# Matrix_Buttons_v0_0_1.net
KiCad netlist of a schematic drawn in Altium Designer
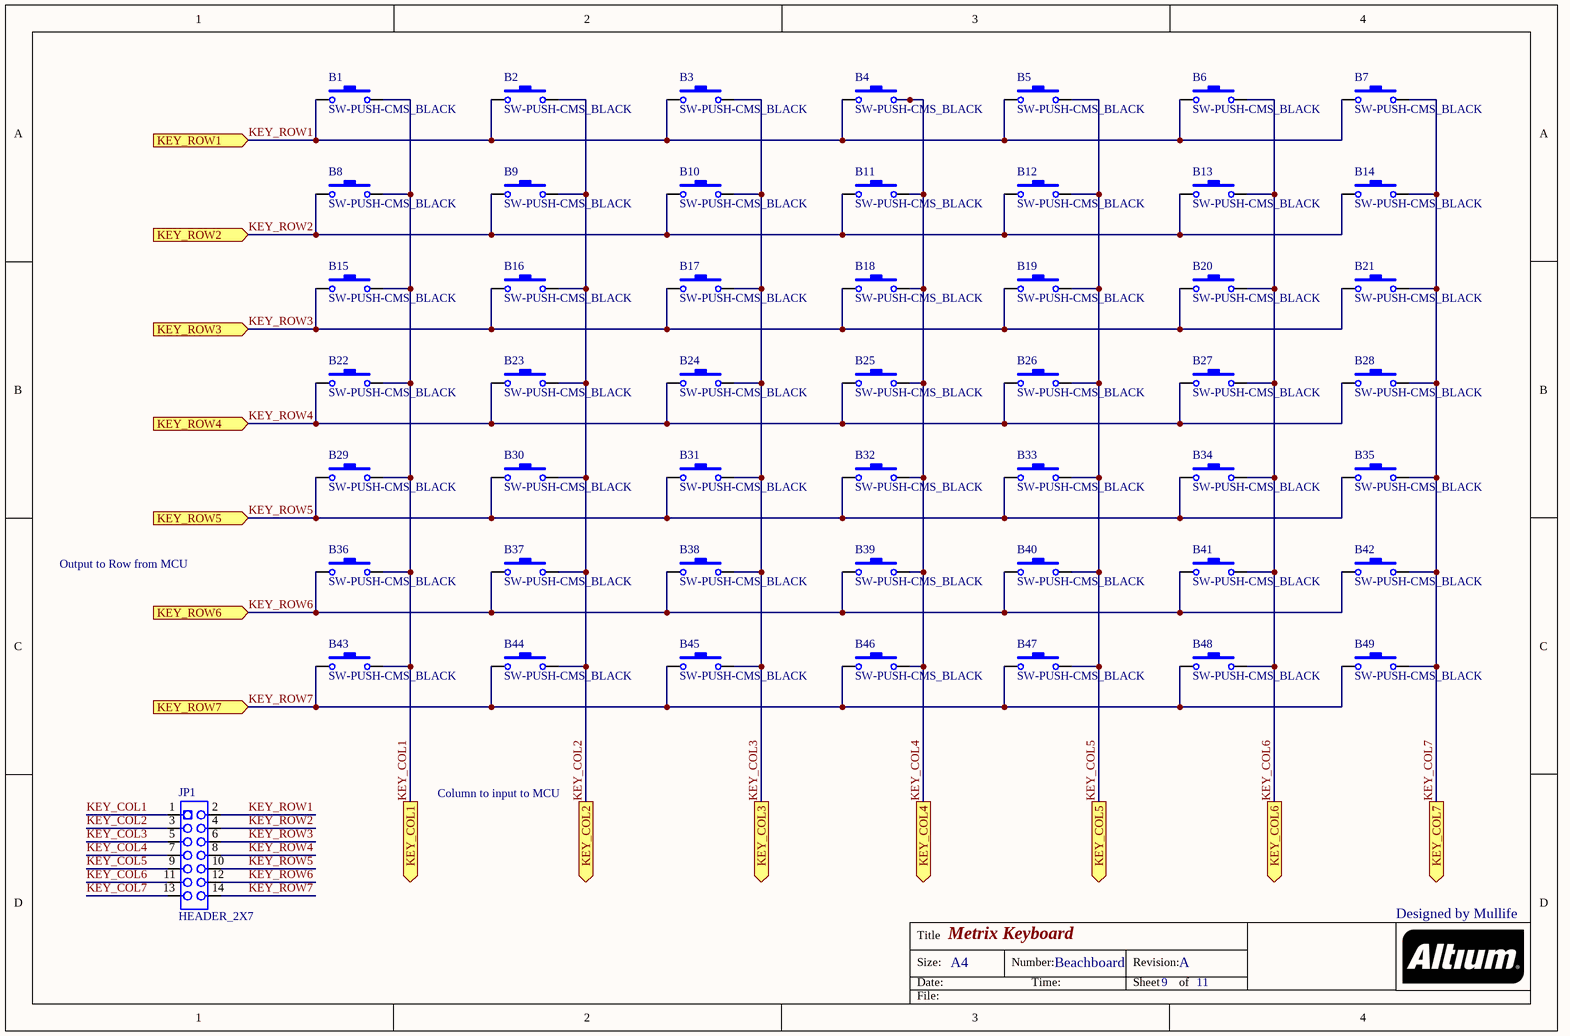
[diagram p0: Matrix_Buttons_v0.0.1.SchDoc]

(export (version "E")
  (design (tool "Eeschema 10.0.6"))
  (components
    (comp (ref "B1")
      (value "SW-PUSH-CMS_BLACK")
      (footprint "SWI_WEALTHMETAL_TD-0341_4P - BACK")
      (description "Push-button SMD")
      (libsource (lib "ST_Lib3D") (part "SW-PB_2"))
    )
    (comp (ref "B2")
      (value "SW-PUSH-CMS_BLACK")
      (footprint "SWI_WEALTHMETAL_TD-0341_4P - BACK")
      (description "Push-button SMD")
      (libsource (lib "ST_Lib3D") (part "SW-PB_2"))
    )
    (comp (ref "B3")
      (value "SW-PUSH-CMS_BLACK")
      (footprint "SWI_WEALTHMETAL_TD-0341_4P - BACK")
      (description "Push-button SMD")
      (libsource (lib "ST_Lib3D") (part "SW-PB_2"))
    )
    (comp (ref "B4")
      (value "SW-PUSH-CMS_BLACK")
      (footprint "SWI_WEALTHMETAL_TD-0341_4P - BACK")
      (description "Push-button SMD")
      (libsource (lib "ST_Lib3D") (part "SW-PB_2"))
    )
    (comp (ref "B5")
      (value "SW-PUSH-CMS_BLACK")
      (footprint "SWI_WEALTHMETAL_TD-0341_4P - BACK")
      (description "Push-button SMD")
      (libsource (lib "ST_Lib3D") (part "SW-PB_2"))
    )
    (comp (ref "B6")
      (value "SW-PUSH-CMS_BLACK")
      (footprint "SWI_WEALTHMETAL_TD-0341_4P - BACK")
      (description "Push-button SMD")
      (libsource (lib "ST_Lib3D") (part "SW-PB_2"))
    )
    (comp (ref "B7")
      (value "SW-PUSH-CMS_BLACK")
      (footprint "SWI_WEALTHMETAL_TD-0341_4P - BACK")
      (description "Push-button SMD")
      (libsource (lib "ST_Lib3D") (part "SW-PB_2"))
    )
    (comp (ref "B8")
      (value "SW-PUSH-CMS_BLACK")
      (footprint "SWI_WEALTHMETAL_TD-0341_4P - BACK")
      (description "Push-button SMD")
      (libsource (lib "ST_Lib3D") (part "SW-PB_2"))
    )
    (comp (ref "B9")
      (value "SW-PUSH-CMS_BLACK")
      (footprint "SWI_WEALTHMETAL_TD-0341_4P - BACK")
      (description "Push-button SMD")
      (libsource (lib "ST_Lib3D") (part "SW-PB_2"))
    )
    (comp (ref "B10")
      (value "SW-PUSH-CMS_BLACK")
      (footprint "SWI_WEALTHMETAL_TD-0341_4P - BACK")
      (description "Push-button SMD")
      (libsource (lib "ST_Lib3D") (part "SW-PB_2"))
    )
    (comp (ref "B11")
      (value "SW-PUSH-CMS_BLACK")
      (footprint "SWI_WEALTHMETAL_TD-0341_4P - BACK")
      (description "Push-button SMD")
      (libsource (lib "ST_Lib3D") (part "SW-PB_2"))
    )
    (comp (ref "B12")
      (value "SW-PUSH-CMS_BLACK")
      (footprint "SWI_WEALTHMETAL_TD-0341_4P - BACK")
      (description "Push-button SMD")
      (libsource (lib "ST_Lib3D") (part "SW-PB_2"))
    )
    (comp (ref "B13")
      (value "SW-PUSH-CMS_BLACK")
      (footprint "SWI_WEALTHMETAL_TD-0341_4P - BACK")
      (description "Push-button SMD")
      (libsource (lib "ST_Lib3D") (part "SW-PB_2"))
    )
    (comp (ref "B14")
      (value "SW-PUSH-CMS_BLACK")
      (footprint "SWI_WEALTHMETAL_TD-0341_4P - BACK")
      (description "Push-button SMD")
      (libsource (lib "ST_Lib3D") (part "SW-PB_2"))
    )
    (comp (ref "B15")
      (value "SW-PUSH-CMS_BLACK")
      (footprint "SWI_WEALTHMETAL_TD-0341_4P - BACK")
      (description "Push-button SMD")
      (libsource (lib "ST_Lib3D") (part "SW-PB_2"))
    )
    (comp (ref "B16")
      (value "SW-PUSH-CMS_BLACK")
      (footprint "SWI_WEALTHMETAL_TD-0341_4P - BACK")
      (description "Push-button SMD")
      (libsource (lib "ST_Lib3D") (part "SW-PB_2"))
    )
    (comp (ref "B17")
      (value "SW-PUSH-CMS_BLACK")
      (footprint "SWI_WEALTHMETAL_TD-0341_4P - BACK")
      (description "Push-button SMD")
      (libsource (lib "ST_Lib3D") (part "SW-PB_2"))
    )
    (comp (ref "B18")
      (value "SW-PUSH-CMS_BLACK")
      (footprint "SWI_WEALTHMETAL_TD-0341_4P - BACK")
      (description "Push-button SMD")
      (libsource (lib "ST_Lib3D") (part "SW-PB_2"))
    )
    (comp (ref "B19")
      (value "SW-PUSH-CMS_BLACK")
      (footprint "SWI_WEALTHMETAL_TD-0341_4P - BACK")
      (description "Push-button SMD")
      (libsource (lib "ST_Lib3D") (part "SW-PB_2"))
    )
    (comp (ref "B20")
      (value "SW-PUSH-CMS_BLACK")
      (footprint "SWI_WEALTHMETAL_TD-0341_4P - BACK")
      (description "Push-button SMD")
      (libsource (lib "ST_Lib3D") (part "SW-PB_2"))
    )
    (comp (ref "B21")
      (value "SW-PUSH-CMS_BLACK")
      (footprint "SWI_WEALTHMETAL_TD-0341_4P - BACK")
      (description "Push-button SMD")
      (libsource (lib "ST_Lib3D") (part "SW-PB_2"))
    )
    (comp (ref "B22")
      (value "SW-PUSH-CMS_BLACK")
      (footprint "SWI_WEALTHMETAL_TD-0341_4P - BACK")
      (description "Push-button SMD")
      (libsource (lib "ST_Lib3D") (part "SW-PB_2"))
    )
    (comp (ref "B23")
      (value "SW-PUSH-CMS_BLACK")
      (footprint "SWI_WEALTHMETAL_TD-0341_4P - BACK")
      (description "Push-button SMD")
      (libsource (lib "ST_Lib3D") (part "SW-PB_2"))
    )
    (comp (ref "B24")
      (value "SW-PUSH-CMS_BLACK")
      (footprint "SWI_WEALTHMETAL_TD-0341_4P - BACK")
      (description "Push-button SMD")
      (libsource (lib "ST_Lib3D") (part "SW-PB_2"))
    )
    (comp (ref "B25")
      (value "SW-PUSH-CMS_BLACK")
      (footprint "SWI_WEALTHMETAL_TD-0341_4P - BACK")
      (description "Push-button SMD")
      (libsource (lib "ST_Lib3D") (part "SW-PB_2"))
    )
    (comp (ref "B26")
      (value "SW-PUSH-CMS_BLACK")
      (footprint "SWI_WEALTHMETAL_TD-0341_4P - BACK")
      (description "Push-button SMD")
      (libsource (lib "ST_Lib3D") (part "SW-PB_2"))
    )
    (comp (ref "B27")
      (value "SW-PUSH-CMS_BLACK")
      (footprint "SWI_WEALTHMETAL_TD-0341_4P - BACK")
      (description "Push-button SMD")
      (libsource (lib "ST_Lib3D") (part "SW-PB_2"))
    )
    (comp (ref "B28")
      (value "SW-PUSH-CMS_BLACK")
      (footprint "SWI_WEALTHMETAL_TD-0341_4P - BACK")
      (description "Push-button SMD")
      (libsource (lib "ST_Lib3D") (part "SW-PB_2"))
    )
    (comp (ref "B29")
      (value "SW-PUSH-CMS_BLACK")
      (footprint "SWI_WEALTHMETAL_TD-0341_4P - BACK")
      (description "Push-button SMD")
      (libsource (lib "ST_Lib3D") (part "SW-PB_2"))
    )
    (comp (ref "B30")
      (value "SW-PUSH-CMS_BLACK")
      (footprint "SWI_WEALTHMETAL_TD-0341_4P - BACK")
      (description "Push-button SMD")
      (libsource (lib "ST_Lib3D") (part "SW-PB_2"))
    )
    (comp (ref "B31")
      (value "SW-PUSH-CMS_BLACK")
      (footprint "SWI_WEALTHMETAL_TD-0341_4P - BACK")
      (description "Push-button SMD")
      (libsource (lib "ST_Lib3D") (part "SW-PB_2"))
    )
    (comp (ref "B32")
      (value "SW-PUSH-CMS_BLACK")
      (footprint "SWI_WEALTHMETAL_TD-0341_4P - BACK")
      (description "Push-button SMD")
      (libsource (lib "ST_Lib3D") (part "SW-PB_2"))
    )
    (comp (ref "B33")
      (value "SW-PUSH-CMS_BLACK")
      (footprint "SWI_WEALTHMETAL_TD-0341_4P - BACK")
      (description "Push-button SMD")
      (libsource (lib "ST_Lib3D") (part "SW-PB_2"))
    )
    (comp (ref "B34")
      (value "SW-PUSH-CMS_BLACK")
      (footprint "SWI_WEALTHMETAL_TD-0341_4P - BACK")
      (description "Push-button SMD")
      (libsource (lib "ST_Lib3D") (part "SW-PB_2"))
    )
    (comp (ref "B35")
      (value "SW-PUSH-CMS_BLACK")
      (footprint "SWI_WEALTHMETAL_TD-0341_4P - BACK")
      (description "Push-button SMD")
      (libsource (lib "ST_Lib3D") (part "SW-PB_2"))
    )
    (comp (ref "B36")
      (value "SW-PUSH-CMS_BLACK")
      (footprint "SWI_WEALTHMETAL_TD-0341_4P - BACK")
      (description "Push-button SMD")
      (libsource (lib "ST_Lib3D") (part "SW-PB_2"))
    )
    (comp (ref "B37")
      (value "SW-PUSH-CMS_BLACK")
      (footprint "SWI_WEALTHMETAL_TD-0341_4P - BACK")
      (description "Push-button SMD")
      (libsource (lib "ST_Lib3D") (part "SW-PB_2"))
    )
    (comp (ref "B38")
      (value "SW-PUSH-CMS_BLACK")
      (footprint "SWI_WEALTHMETAL_TD-0341_4P - BACK")
      (description "Push-button SMD")
      (libsource (lib "ST_Lib3D") (part "SW-PB_2"))
    )
    (comp (ref "B39")
      (value "SW-PUSH-CMS_BLACK")
      (footprint "SWI_WEALTHMETAL_TD-0341_4P - BACK")
      (description "Push-button SMD")
      (libsource (lib "ST_Lib3D") (part "SW-PB_2"))
    )
    (comp (ref "B40")
      (value "SW-PUSH-CMS_BLACK")
      (footprint "SWI_WEALTHMETAL_TD-0341_4P - BACK")
      (description "Push-button SMD")
      (libsource (lib "ST_Lib3D") (part "SW-PB_2"))
    )
    (comp (ref "B41")
      (value "SW-PUSH-CMS_BLACK")
      (footprint "SWI_WEALTHMETAL_TD-0341_4P - BACK")
      (description "Push-button SMD")
      (libsource (lib "ST_Lib3D") (part "SW-PB_2"))
    )
    (comp (ref "B42")
      (value "SW-PUSH-CMS_BLACK")
      (footprint "SWI_WEALTHMETAL_TD-0341_4P - BACK")
      (description "Push-button SMD")
      (libsource (lib "ST_Lib3D") (part "SW-PB_2"))
    )
    (comp (ref "B43")
      (value "SW-PUSH-CMS_BLACK")
      (footprint "SWI_WEALTHMETAL_TD-0341_4P - BACK")
      (description "Push-button SMD")
      (libsource (lib "ST_Lib3D") (part "SW-PB_2"))
    )
    (comp (ref "B44")
      (value "SW-PUSH-CMS_BLACK")
      (footprint "SWI_WEALTHMETAL_TD-0341_4P - BACK")
      (description "Push-button SMD")
      (libsource (lib "ST_Lib3D") (part "SW-PB_2"))
    )
    (comp (ref "B45")
      (value "SW-PUSH-CMS_BLACK")
      (footprint "SWI_WEALTHMETAL_TD-0341_4P - BACK")
      (description "Push-button SMD")
      (libsource (lib "ST_Lib3D") (part "SW-PB_2"))
    )
    (comp (ref "B46")
      (value "SW-PUSH-CMS_BLACK")
      (footprint "SWI_WEALTHMETAL_TD-0341_4P - BACK")
      (description "Push-button SMD")
      (libsource (lib "ST_Lib3D") (part "SW-PB_2"))
    )
    (comp (ref "B47")
      (value "SW-PUSH-CMS_BLACK")
      (footprint "SWI_WEALTHMETAL_TD-0341_4P - BACK")
      (description "Push-button SMD")
      (libsource (lib "ST_Lib3D") (part "SW-PB_2"))
    )
    (comp (ref "B48")
      (value "SW-PUSH-CMS_BLACK")
      (footprint "SWI_WEALTHMETAL_TD-0341_4P - BACK")
      (description "Push-button SMD")
      (libsource (lib "ST_Lib3D") (part "SW-PB_2"))
    )
    (comp (ref "B49")
      (value "SW-PUSH-CMS_BLACK")
      (footprint "SWI_WEALTHMETAL_TD-0341_4P - BACK")
      (description "Push-button SMD")
      (libsource (lib "ST_Lib3D") (part "SW-PB_2"))
    )
    (comp (ref "JP1")
      (value "HEADER_2X7")
      (footprint "Header M 2x7x2.54 TH V")
      (libsource (lib "Mullife_SCH") (part "HEADER_2X7"))
    )
  )
  (nets
    (net (code "1") (name "/KEY_COL1") (class "Default")
      (node (ref "B1") (pin "2") (pinfunction "2_2") (pintype "passive"))
      (node (ref "B15") (pin "2") (pinfunction "2_2") (pintype "passive"))
      (node (ref "B22") (pin "2") (pinfunction "2_2") (pintype "passive"))
      (node (ref "B29") (pin "2") (pinfunction "2_2") (pintype "passive"))
      (node (ref "B36") (pin "2") (pinfunction "2_2") (pintype "passive"))
      (node (ref "B43") (pin "2") (pinfunction "2_2") (pintype "passive"))
      (node (ref "B8") (pin "2") (pinfunction "2_2") (pintype "passive"))
      (node (ref "JP1") (pin "1") (pinfunction "1_1") (pintype "passive"))
    )
    (net (code "2") (name "/KEY_COL2") (class "Default")
      (node (ref "B16") (pin "2") (pinfunction "2_2") (pintype "passive"))
      (node (ref "B2") (pin "2") (pinfunction "2_2") (pintype "passive"))
      (node (ref "B23") (pin "2") (pinfunction "2_2") (pintype "passive"))
      (node (ref "B30") (pin "2") (pinfunction "2_2") (pintype "passive"))
      (node (ref "B37") (pin "2") (pinfunction "2_2") (pintype "passive"))
      (node (ref "B44") (pin "2") (pinfunction "2_2") (pintype "passive"))
      (node (ref "B9") (pin "2") (pinfunction "2_2") (pintype "passive"))
      (node (ref "JP1") (pin "3") (pinfunction "3_3") (pintype "passive"))
    )
    (net (code "3") (name "/KEY_COL3") (class "Default")
      (node (ref "B10") (pin "2") (pinfunction "2_2") (pintype "passive"))
      (node (ref "B17") (pin "2") (pinfunction "2_2") (pintype "passive"))
      (node (ref "B24") (pin "2") (pinfunction "2_2") (pintype "passive"))
      (node (ref "B3") (pin "2") (pinfunction "2_2") (pintype "passive"))
      (node (ref "B31") (pin "2") (pinfunction "2_2") (pintype "passive"))
      (node (ref "B38") (pin "2") (pinfunction "2_2") (pintype "passive"))
      (node (ref "B45") (pin "2") (pinfunction "2_2") (pintype "passive"))
      (node (ref "JP1") (pin "5") (pinfunction "5_5") (pintype "passive"))
    )
    (net (code "4") (name "/KEY_COL4") (class "Default")
      (node (ref "B11") (pin "2") (pinfunction "2_2") (pintype "passive"))
      (node (ref "B18") (pin "2") (pinfunction "2_2") (pintype "passive"))
      (node (ref "B25") (pin "2") (pinfunction "2_2") (pintype "passive"))
      (node (ref "B32") (pin "2") (pinfunction "2_2") (pintype "passive"))
      (node (ref "B39") (pin "2") (pinfunction "2_2") (pintype "passive"))
      (node (ref "B4") (pin "2") (pinfunction "2_2") (pintype "passive"))
      (node (ref "B46") (pin "2") (pinfunction "2_2") (pintype "passive"))
      (node (ref "JP1") (pin "7") (pinfunction "7_7") (pintype "passive"))
    )
    (net (code "5") (name "/KEY_COL5") (class "Default")
      (node (ref "B12") (pin "2") (pinfunction "2_2") (pintype "passive"))
      (node (ref "B19") (pin "2") (pinfunction "2_2") (pintype "passive"))
      (node (ref "B26") (pin "2") (pinfunction "2_2") (pintype "passive"))
      (node (ref "B33") (pin "2") (pinfunction "2_2") (pintype "passive"))
      (node (ref "B40") (pin "2") (pinfunction "2_2") (pintype "passive"))
      (node (ref "B47") (pin "2") (pinfunction "2_2") (pintype "passive"))
      (node (ref "B5") (pin "2") (pinfunction "2_2") (pintype "passive"))
      (node (ref "JP1") (pin "9") (pinfunction "9_9") (pintype "passive"))
    )
    (net (code "6") (name "/KEY_COL6") (class "Default")
      (node (ref "B13") (pin "2") (pinfunction "2_2") (pintype "passive"))
      (node (ref "B20") (pin "2") (pinfunction "2_2") (pintype "passive"))
      (node (ref "B27") (pin "2") (pinfunction "2_2") (pintype "passive"))
      (node (ref "B34") (pin "2") (pinfunction "2_2") (pintype "passive"))
      (node (ref "B41") (pin "2") (pinfunction "2_2") (pintype "passive"))
      (node (ref "B48") (pin "2") (pinfunction "2_2") (pintype "passive"))
      (node (ref "B6") (pin "2") (pinfunction "2_2") (pintype "passive"))
      (node (ref "JP1") (pin "11") (pinfunction "11_11") (pintype "passive"))
    )
    (net (code "7") (name "/KEY_COL7") (class "Default")
      (node (ref "B14") (pin "2") (pinfunction "2_2") (pintype "passive"))
      (node (ref "B21") (pin "2") (pinfunction "2_2") (pintype "passive"))
      (node (ref "B28") (pin "2") (pinfunction "2_2") (pintype "passive"))
      (node (ref "B35") (pin "2") (pinfunction "2_2") (pintype "passive"))
      (node (ref "B42") (pin "2") (pinfunction "2_2") (pintype "passive"))
      (node (ref "B49") (pin "2") (pinfunction "2_2") (pintype "passive"))
      (node (ref "B7") (pin "2") (pinfunction "2_2") (pintype "passive"))
      (node (ref "JP1") (pin "13") (pinfunction "13_13") (pintype "passive"))
    )
    (net (code "8") (name "/KEY_ROW1") (class "Default")
      (node (ref "B1") (pin "1") (pinfunction "1_1") (pintype "passive"))
      (node (ref "B2") (pin "1") (pinfunction "1_1") (pintype "passive"))
      (node (ref "B3") (pin "1") (pinfunction "1_1") (pintype "passive"))
      (node (ref "B4") (pin "1") (pinfunction "1_1") (pintype "passive"))
      (node (ref "B5") (pin "1") (pinfunction "1_1") (pintype "passive"))
      (node (ref "B6") (pin "1") (pinfunction "1_1") (pintype "passive"))
      (node (ref "B7") (pin "1") (pinfunction "1_1") (pintype "passive"))
      (node (ref "JP1") (pin "2") (pinfunction "2_2") (pintype "passive"))
    )
    (net (code "9") (name "/KEY_ROW2") (class "Default")
      (node (ref "B10") (pin "1") (pinfunction "1_1") (pintype "passive"))
      (node (ref "B11") (pin "1") (pinfunction "1_1") (pintype "passive"))
      (node (ref "B12") (pin "1") (pinfunction "1_1") (pintype "passive"))
      (node (ref "B13") (pin "1") (pinfunction "1_1") (pintype "passive"))
      (node (ref "B14") (pin "1") (pinfunction "1_1") (pintype "passive"))
      (node (ref "B8") (pin "1") (pinfunction "1_1") (pintype "passive"))
      (node (ref "B9") (pin "1") (pinfunction "1_1") (pintype "passive"))
      (node (ref "JP1") (pin "4") (pinfunction "4_4") (pintype "passive"))
    )
    (net (code "10") (name "/KEY_ROW3") (class "Default")
      (node (ref "B15") (pin "1") (pinfunction "1_1") (pintype "passive"))
      (node (ref "B16") (pin "1") (pinfunction "1_1") (pintype "passive"))
      (node (ref "B17") (pin "1") (pinfunction "1_1") (pintype "passive"))
      (node (ref "B18") (pin "1") (pinfunction "1_1") (pintype "passive"))
      (node (ref "B19") (pin "1") (pinfunction "1_1") (pintype "passive"))
      (node (ref "B20") (pin "1") (pinfunction "1_1") (pintype "passive"))
      (node (ref "B21") (pin "1") (pinfunction "1_1") (pintype "passive"))
      (node (ref "JP1") (pin "6") (pinfunction "6_6") (pintype "passive"))
    )
    (net (code "11") (name "/KEY_ROW4") (class "Default")
      (node (ref "B22") (pin "1") (pinfunction "1_1") (pintype "passive"))
      (node (ref "B23") (pin "1") (pinfunction "1_1") (pintype "passive"))
      (node (ref "B24") (pin "1") (pinfunction "1_1") (pintype "passive"))
      (node (ref "B25") (pin "1") (pinfunction "1_1") (pintype "passive"))
      (node (ref "B26") (pin "1") (pinfunction "1_1") (pintype "passive"))
      (node (ref "B27") (pin "1") (pinfunction "1_1") (pintype "passive"))
      (node (ref "B28") (pin "1") (pinfunction "1_1") (pintype "passive"))
      (node (ref "JP1") (pin "8") (pinfunction "8_8") (pintype "passive"))
    )
    (net (code "12") (name "/KEY_ROW5") (class "Default")
      (node (ref "B29") (pin "1") (pinfunction "1_1") (pintype "passive"))
      (node (ref "B30") (pin "1") (pinfunction "1_1") (pintype "passive"))
      (node (ref "B31") (pin "1") (pinfunction "1_1") (pintype "passive"))
      (node (ref "B32") (pin "1") (pinfunction "1_1") (pintype "passive"))
      (node (ref "B33") (pin "1") (pinfunction "1_1") (pintype "passive"))
      (node (ref "B34") (pin "1") (pinfunction "1_1") (pintype "passive"))
      (node (ref "B35") (pin "1") (pinfunction "1_1") (pintype "passive"))
      (node (ref "JP1") (pin "10") (pinfunction "10_10") (pintype "passive"))
    )
    (net (code "13") (name "/KEY_ROW6") (class "Default")
      (node (ref "B36") (pin "1") (pinfunction "1_1") (pintype "passive"))
      (node (ref "B37") (pin "1") (pinfunction "1_1") (pintype "passive"))
      (node (ref "B38") (pin "1") (pinfunction "1_1") (pintype "passive"))
      (node (ref "B39") (pin "1") (pinfunction "1_1") (pintype "passive"))
      (node (ref "B40") (pin "1") (pinfunction "1_1") (pintype "passive"))
      (node (ref "B41") (pin "1") (pinfunction "1_1") (pintype "passive"))
      (node (ref "B42") (pin "1") (pinfunction "1_1") (pintype "passive"))
      (node (ref "JP1") (pin "12") (pinfunction "12_12") (pintype "passive"))
    )
    (net (code "14") (name "/KEY_ROW7") (class "Default")
      (node (ref "B43") (pin "1") (pinfunction "1_1") (pintype "passive"))
      (node (ref "B44") (pin "1") (pinfunction "1_1") (pintype "passive"))
      (node (ref "B45") (pin "1") (pinfunction "1_1") (pintype "passive"))
      (node (ref "B46") (pin "1") (pinfunction "1_1") (pintype "passive"))
      (node (ref "B47") (pin "1") (pinfunction "1_1") (pintype "passive"))
      (node (ref "B48") (pin "1") (pinfunction "1_1") (pintype "passive"))
      (node (ref "B49") (pin "1") (pinfunction "1_1") (pintype "passive"))
      (node (ref "JP1") (pin "14") (pinfunction "14_14") (pintype "passive"))
    )
  )
)
